# RoboRio_LED_schematic.net
KiCad netlist of a schematic drawn in EAGLE
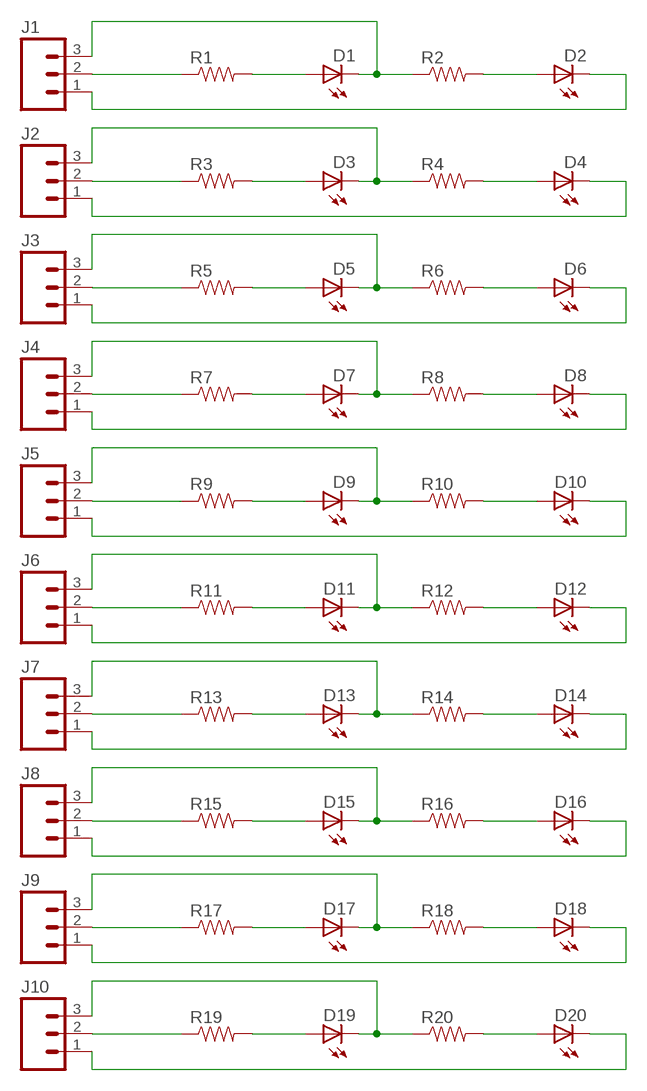
[diagram p0: schematic, sheet 1]

(export (version "E")
  (design (tool "Eeschema 10.0.6"))
  (components
    (comp (ref "D1")
      (value "LED1206")
      (footprint "eagle-import:LED-1206")
      (libsource (lib "eagle-import") (part "LED1206"))
    )
    (comp (ref "D2")
      (value "LED1206")
      (footprint "eagle-import:LED-1206")
      (libsource (lib "eagle-import") (part "LED1206"))
    )
    (comp (ref "D3")
      (value "LED1206")
      (footprint "eagle-import:LED-1206")
      (libsource (lib "eagle-import") (part "LED1206"))
    )
    (comp (ref "D4")
      (value "LED1206")
      (footprint "eagle-import:LED-1206")
      (libsource (lib "eagle-import") (part "LED1206"))
    )
    (comp (ref "D5")
      (value "LED1206")
      (footprint "eagle-import:LED-1206")
      (libsource (lib "eagle-import") (part "LED1206"))
    )
    (comp (ref "D6")
      (value "LED1206")
      (footprint "eagle-import:LED-1206")
      (libsource (lib "eagle-import") (part "LED1206"))
    )
    (comp (ref "D7")
      (value "LED1206")
      (footprint "eagle-import:LED-1206")
      (libsource (lib "eagle-import") (part "LED1206"))
    )
    (comp (ref "D8")
      (value "LED1206")
      (footprint "eagle-import:LED-1206")
      (libsource (lib "eagle-import") (part "LED1206"))
    )
    (comp (ref "D9")
      (value "LED1206")
      (footprint "eagle-import:LED-1206")
      (libsource (lib "eagle-import") (part "LED1206"))
    )
    (comp (ref "D10")
      (value "LED1206")
      (footprint "eagle-import:LED-1206")
      (libsource (lib "eagle-import") (part "LED1206"))
    )
    (comp (ref "D11")
      (value "LED1206")
      (footprint "eagle-import:LED-1206")
      (libsource (lib "eagle-import") (part "LED1206"))
    )
    (comp (ref "D12")
      (value "LED1206")
      (footprint "eagle-import:LED-1206")
      (libsource (lib "eagle-import") (part "LED1206"))
    )
    (comp (ref "D13")
      (value "LED1206")
      (footprint "eagle-import:LED-1206")
      (libsource (lib "eagle-import") (part "LED1206"))
    )
    (comp (ref "D14")
      (value "LED1206")
      (footprint "eagle-import:LED-1206")
      (libsource (lib "eagle-import") (part "LED1206"))
    )
    (comp (ref "D15")
      (value "LED1206")
      (footprint "eagle-import:LED-1206")
      (libsource (lib "eagle-import") (part "LED1206"))
    )
    (comp (ref "D16")
      (value "LED1206")
      (footprint "eagle-import:LED-1206")
      (libsource (lib "eagle-import") (part "LED1206"))
    )
    (comp (ref "D17")
      (value "LED1206")
      (footprint "eagle-import:LED-1206")
      (libsource (lib "eagle-import") (part "LED1206"))
    )
    (comp (ref "D18")
      (value "LED1206")
      (footprint "eagle-import:LED-1206")
      (libsource (lib "eagle-import") (part "LED1206"))
    )
    (comp (ref "D19")
      (value "LED1206")
      (footprint "eagle-import:LED-1206")
      (libsource (lib "eagle-import") (part "LED1206"))
    )
    (comp (ref "D20")
      (value "LED1206")
      (footprint "eagle-import:LED-1206")
      (libsource (lib "eagle-import") (part "LED1206"))
    )
    (comp (ref "J1")
      (value "M03PTH")
      (footprint "eagle-import:1X03")
      (libsource (lib "eagle-import") (part "M03PTH"))
    )
    (comp (ref "J2")
      (value "M03PTH")
      (footprint "eagle-import:1X03")
      (libsource (lib "eagle-import") (part "M03PTH"))
    )
    (comp (ref "J3")
      (value "M03PTH")
      (footprint "eagle-import:1X03")
      (libsource (lib "eagle-import") (part "M03PTH"))
    )
    (comp (ref "J4")
      (value "M03PTH")
      (footprint "eagle-import:1X03")
      (libsource (lib "eagle-import") (part "M03PTH"))
    )
    (comp (ref "J5")
      (value "M03PTH")
      (footprint "eagle-import:1X03")
      (libsource (lib "eagle-import") (part "M03PTH"))
    )
    (comp (ref "J6")
      (value "M03PTH")
      (footprint "eagle-import:1X03")
      (libsource (lib "eagle-import") (part "M03PTH"))
    )
    (comp (ref "J7")
      (value "M03PTH")
      (footprint "eagle-import:1X03")
      (libsource (lib "eagle-import") (part "M03PTH"))
    )
    (comp (ref "J8")
      (value "M03PTH")
      (footprint "eagle-import:1X03")
      (libsource (lib "eagle-import") (part "M03PTH"))
    )
    (comp (ref "J9")
      (value "M03PTH")
      (footprint "eagle-import:1X03")
      (libsource (lib "eagle-import") (part "M03PTH"))
    )
    (comp (ref "J10")
      (value "M03PTH")
      (footprint "eagle-import:1X03")
      (libsource (lib "eagle-import") (part "M03PTH"))
    )
    (comp (ref "R1")
      (value "RESISTOR0603-RES")
      (footprint "eagle-import:0603-RES")
      (libsource (lib "eagle-import") (part "RESISTOR0603-RES"))
    )
    (comp (ref "R2")
      (value "RESISTOR0603-RES")
      (footprint "eagle-import:0603-RES")
      (libsource (lib "eagle-import") (part "RESISTOR0603-RES"))
    )
    (comp (ref "R3")
      (value "RESISTOR0603-RES")
      (footprint "eagle-import:0603-RES")
      (libsource (lib "eagle-import") (part "RESISTOR0603-RES"))
    )
    (comp (ref "R4")
      (value "RESISTOR0603-RES")
      (footprint "eagle-import:0603-RES")
      (libsource (lib "eagle-import") (part "RESISTOR0603-RES"))
    )
    (comp (ref "R5")
      (value "RESISTOR0603-RES")
      (footprint "eagle-import:0603-RES")
      (libsource (lib "eagle-import") (part "RESISTOR0603-RES"))
    )
    (comp (ref "R6")
      (value "RESISTOR0603-RES")
      (footprint "eagle-import:0603-RES")
      (libsource (lib "eagle-import") (part "RESISTOR0603-RES"))
    )
    (comp (ref "R7")
      (value "RESISTOR0603-RES")
      (footprint "eagle-import:0603-RES")
      (libsource (lib "eagle-import") (part "RESISTOR0603-RES"))
    )
    (comp (ref "R8")
      (value "RESISTOR0603-RES")
      (footprint "eagle-import:0603-RES")
      (libsource (lib "eagle-import") (part "RESISTOR0603-RES"))
    )
    (comp (ref "R9")
      (value "RESISTOR0603-RES")
      (footprint "eagle-import:0603-RES")
      (libsource (lib "eagle-import") (part "RESISTOR0603-RES"))
    )
    (comp (ref "R10")
      (value "RESISTOR0603-RES")
      (footprint "eagle-import:0603-RES")
      (libsource (lib "eagle-import") (part "RESISTOR0603-RES"))
    )
    (comp (ref "R11")
      (value "RESISTOR0603-RES")
      (footprint "eagle-import:0603-RES")
      (libsource (lib "eagle-import") (part "RESISTOR0603-RES"))
    )
    (comp (ref "R12")
      (value "RESISTOR0603-RES")
      (footprint "eagle-import:0603-RES")
      (libsource (lib "eagle-import") (part "RESISTOR0603-RES"))
    )
    (comp (ref "R13")
      (value "RESISTOR0603-RES")
      (footprint "eagle-import:0603-RES")
      (libsource (lib "eagle-import") (part "RESISTOR0603-RES"))
    )
    (comp (ref "R14")
      (value "RESISTOR0603-RES")
      (footprint "eagle-import:0603-RES")
      (libsource (lib "eagle-import") (part "RESISTOR0603-RES"))
    )
    (comp (ref "R15")
      (value "RESISTOR0603-RES")
      (footprint "eagle-import:0603-RES")
      (libsource (lib "eagle-import") (part "RESISTOR0603-RES"))
    )
    (comp (ref "R16")
      (value "RESISTOR0603-RES")
      (footprint "eagle-import:0603-RES")
      (libsource (lib "eagle-import") (part "RESISTOR0603-RES"))
    )
    (comp (ref "R17")
      (value "RESISTOR0603-RES")
      (footprint "eagle-import:0603-RES")
      (libsource (lib "eagle-import") (part "RESISTOR0603-RES"))
    )
    (comp (ref "R18")
      (value "RESISTOR0603-RES")
      (footprint "eagle-import:0603-RES")
      (libsource (lib "eagle-import") (part "RESISTOR0603-RES"))
    )
    (comp (ref "R19")
      (value "RESISTOR0603-RES")
      (footprint "eagle-import:0603-RES")
      (libsource (lib "eagle-import") (part "RESISTOR0603-RES"))
    )
    (comp (ref "R20")
      (value "RESISTOR0603-RES")
      (footprint "eagle-import:0603-RES")
      (libsource (lib "eagle-import") (part "RESISTOR0603-RES"))
    )
  )
  (nets
    (net (code "1") (name "Net-(D1-PadA)") (class "Default")
      (node (ref "D1") (pin "A") (pinfunction "A_A") (pintype "passive"))
      (node (ref "R1") (pin "2") (pinfunction "2_2") (pintype "passive"))
    )
    (net (code "2") (name "Net-(D1-PadC)") (class "Default")
      (node (ref "D1") (pin "C") (pinfunction "C_C") (pintype "passive"))
      (node (ref "J1") (pin "3") (pinfunction "3_3") (pintype "passive"))
      (node (ref "R2") (pin "1") (pinfunction "1_1") (pintype "passive"))
    )
    (net (code "3") (name "Net-(D2-PadA)") (class "Default")
      (node (ref "D2") (pin "A") (pinfunction "A_A") (pintype "passive"))
      (node (ref "R2") (pin "2") (pinfunction "2_2") (pintype "passive"))
    )
    (net (code "4") (name "Net-(D2-PadC)") (class "Default")
      (node (ref "D2") (pin "C") (pinfunction "C_C") (pintype "passive"))
      (node (ref "J1") (pin "1") (pinfunction "1_1") (pintype "passive"))
    )
    (net (code "5") (name "Net-(D3-PadA)") (class "Default")
      (node (ref "D3") (pin "A") (pinfunction "A_A") (pintype "passive"))
      (node (ref "R3") (pin "2") (pinfunction "2_2") (pintype "passive"))
    )
    (net (code "6") (name "Net-(D3-PadC)") (class "Default")
      (node (ref "D3") (pin "C") (pinfunction "C_C") (pintype "passive"))
      (node (ref "J2") (pin "3") (pinfunction "3_3") (pintype "passive"))
      (node (ref "R4") (pin "1") (pinfunction "1_1") (pintype "passive"))
    )
    (net (code "7") (name "Net-(D4-PadA)") (class "Default")
      (node (ref "D4") (pin "A") (pinfunction "A_A") (pintype "passive"))
      (node (ref "R4") (pin "2") (pinfunction "2_2") (pintype "passive"))
    )
    (net (code "8") (name "Net-(D4-PadC)") (class "Default")
      (node (ref "D4") (pin "C") (pinfunction "C_C") (pintype "passive"))
      (node (ref "J2") (pin "1") (pinfunction "1_1") (pintype "passive"))
    )
    (net (code "9") (name "Net-(D5-PadA)") (class "Default")
      (node (ref "D5") (pin "A") (pinfunction "A_A") (pintype "passive"))
      (node (ref "R5") (pin "2") (pinfunction "2_2") (pintype "passive"))
    )
    (net (code "10") (name "Net-(D5-PadC)") (class "Default")
      (node (ref "D5") (pin "C") (pinfunction "C_C") (pintype "passive"))
      (node (ref "J3") (pin "3") (pinfunction "3_3") (pintype "passive"))
      (node (ref "R6") (pin "1") (pinfunction "1_1") (pintype "passive"))
    )
    (net (code "11") (name "Net-(D6-PadA)") (class "Default")
      (node (ref "D6") (pin "A") (pinfunction "A_A") (pintype "passive"))
      (node (ref "R6") (pin "2") (pinfunction "2_2") (pintype "passive"))
    )
    (net (code "12") (name "Net-(D6-PadC)") (class "Default")
      (node (ref "D6") (pin "C") (pinfunction "C_C") (pintype "passive"))
      (node (ref "J3") (pin "1") (pinfunction "1_1") (pintype "passive"))
    )
    (net (code "13") (name "Net-(D7-PadA)") (class "Default")
      (node (ref "D7") (pin "A") (pinfunction "A_A") (pintype "passive"))
      (node (ref "R7") (pin "2") (pinfunction "2_2") (pintype "passive"))
    )
    (net (code "14") (name "Net-(D7-PadC)") (class "Default")
      (node (ref "D7") (pin "C") (pinfunction "C_C") (pintype "passive"))
      (node (ref "J4") (pin "3") (pinfunction "3_3") (pintype "passive"))
      (node (ref "R8") (pin "1") (pinfunction "1_1") (pintype "passive"))
    )
    (net (code "15") (name "Net-(D8-PadA)") (class "Default")
      (node (ref "D8") (pin "A") (pinfunction "A_A") (pintype "passive"))
      (node (ref "R8") (pin "2") (pinfunction "2_2") (pintype "passive"))
    )
    (net (code "16") (name "Net-(D8-PadC)") (class "Default")
      (node (ref "D8") (pin "C") (pinfunction "C_C") (pintype "passive"))
      (node (ref "J4") (pin "1") (pinfunction "1_1") (pintype "passive"))
    )
    (net (code "17") (name "Net-(D9-PadA)") (class "Default")
      (node (ref "D9") (pin "A") (pinfunction "A_A") (pintype "passive"))
      (node (ref "R9") (pin "2") (pinfunction "2_2") (pintype "passive"))
    )
    (net (code "18") (name "Net-(D9-PadC)") (class "Default")
      (node (ref "D9") (pin "C") (pinfunction "C_C") (pintype "passive"))
      (node (ref "J5") (pin "3") (pinfunction "3_3") (pintype "passive"))
      (node (ref "R10") (pin "1") (pinfunction "1_1") (pintype "passive"))
    )
    (net (code "19") (name "Net-(D10-PadA)") (class "Default")
      (node (ref "D10") (pin "A") (pinfunction "A_A") (pintype "passive"))
      (node (ref "R10") (pin "2") (pinfunction "2_2") (pintype "passive"))
    )
    (net (code "20") (name "Net-(D10-PadC)") (class "Default")
      (node (ref "D10") (pin "C") (pinfunction "C_C") (pintype "passive"))
      (node (ref "J5") (pin "1") (pinfunction "1_1") (pintype "passive"))
    )
    (net (code "21") (name "Net-(D11-PadA)") (class "Default")
      (node (ref "D11") (pin "A") (pinfunction "A_A") (pintype "passive"))
      (node (ref "R11") (pin "2") (pinfunction "2_2") (pintype "passive"))
    )
    (net (code "22") (name "Net-(D11-PadC)") (class "Default")
      (node (ref "D11") (pin "C") (pinfunction "C_C") (pintype "passive"))
      (node (ref "J6") (pin "3") (pinfunction "3_3") (pintype "passive"))
      (node (ref "R12") (pin "1") (pinfunction "1_1") (pintype "passive"))
    )
    (net (code "23") (name "Net-(D12-PadA)") (class "Default")
      (node (ref "D12") (pin "A") (pinfunction "A_A") (pintype "passive"))
      (node (ref "R12") (pin "2") (pinfunction "2_2") (pintype "passive"))
    )
    (net (code "24") (name "Net-(D12-PadC)") (class "Default")
      (node (ref "D12") (pin "C") (pinfunction "C_C") (pintype "passive"))
      (node (ref "J6") (pin "1") (pinfunction "1_1") (pintype "passive"))
    )
    (net (code "25") (name "Net-(D13-PadA)") (class "Default")
      (node (ref "D13") (pin "A") (pinfunction "A_A") (pintype "passive"))
      (node (ref "R13") (pin "2") (pinfunction "2_2") (pintype "passive"))
    )
    (net (code "26") (name "Net-(D13-PadC)") (class "Default")
      (node (ref "D13") (pin "C") (pinfunction "C_C") (pintype "passive"))
      (node (ref "J7") (pin "3") (pinfunction "3_3") (pintype "passive"))
      (node (ref "R14") (pin "1") (pinfunction "1_1") (pintype "passive"))
    )
    (net (code "27") (name "Net-(D14-PadA)") (class "Default")
      (node (ref "D14") (pin "A") (pinfunction "A_A") (pintype "passive"))
      (node (ref "R14") (pin "2") (pinfunction "2_2") (pintype "passive"))
    )
    (net (code "28") (name "Net-(D14-PadC)") (class "Default")
      (node (ref "D14") (pin "C") (pinfunction "C_C") (pintype "passive"))
      (node (ref "J7") (pin "1") (pinfunction "1_1") (pintype "passive"))
    )
    (net (code "29") (name "Net-(D15-PadA)") (class "Default")
      (node (ref "D15") (pin "A") (pinfunction "A_A") (pintype "passive"))
      (node (ref "R15") (pin "2") (pinfunction "2_2") (pintype "passive"))
    )
    (net (code "30") (name "Net-(D15-PadC)") (class "Default")
      (node (ref "D15") (pin "C") (pinfunction "C_C") (pintype "passive"))
      (node (ref "J8") (pin "3") (pinfunction "3_3") (pintype "passive"))
      (node (ref "R16") (pin "1") (pinfunction "1_1") (pintype "passive"))
    )
    (net (code "31") (name "Net-(D16-PadA)") (class "Default")
      (node (ref "D16") (pin "A") (pinfunction "A_A") (pintype "passive"))
      (node (ref "R16") (pin "2") (pinfunction "2_2") (pintype "passive"))
    )
    (net (code "32") (name "Net-(D16-PadC)") (class "Default")
      (node (ref "D16") (pin "C") (pinfunction "C_C") (pintype "passive"))
      (node (ref "J8") (pin "1") (pinfunction "1_1") (pintype "passive"))
    )
    (net (code "33") (name "Net-(D17-PadA)") (class "Default")
      (node (ref "D17") (pin "A") (pinfunction "A_A") (pintype "passive"))
      (node (ref "R17") (pin "2") (pinfunction "2_2") (pintype "passive"))
    )
    (net (code "34") (name "Net-(D17-PadC)") (class "Default")
      (node (ref "D17") (pin "C") (pinfunction "C_C") (pintype "passive"))
      (node (ref "J9") (pin "3") (pinfunction "3_3") (pintype "passive"))
      (node (ref "R18") (pin "1") (pinfunction "1_1") (pintype "passive"))
    )
    (net (code "35") (name "Net-(D18-PadA)") (class "Default")
      (node (ref "D18") (pin "A") (pinfunction "A_A") (pintype "passive"))
      (node (ref "R18") (pin "2") (pinfunction "2_2") (pintype "passive"))
    )
    (net (code "36") (name "Net-(D18-PadC)") (class "Default")
      (node (ref "D18") (pin "C") (pinfunction "C_C") (pintype "passive"))
      (node (ref "J9") (pin "1") (pinfunction "1_1") (pintype "passive"))
    )
    (net (code "37") (name "Net-(D19-PadA)") (class "Default")
      (node (ref "D19") (pin "A") (pinfunction "A_A") (pintype "passive"))
      (node (ref "R19") (pin "2") (pinfunction "2_2") (pintype "passive"))
    )
    (net (code "38") (name "Net-(D19-PadC)") (class "Default")
      (node (ref "D19") (pin "C") (pinfunction "C_C") (pintype "passive"))
      (node (ref "J10") (pin "3") (pinfunction "3_3") (pintype "passive"))
      (node (ref "R20") (pin "1") (pinfunction "1_1") (pintype "passive"))
    )
    (net (code "39") (name "Net-(D20-PadA)") (class "Default")
      (node (ref "D20") (pin "A") (pinfunction "A_A") (pintype "passive"))
      (node (ref "R20") (pin "2") (pinfunction "2_2") (pintype "passive"))
    )
    (net (code "40") (name "Net-(D20-PadC)") (class "Default")
      (node (ref "D20") (pin "C") (pinfunction "C_C") (pintype "passive"))
      (node (ref "J10") (pin "1") (pinfunction "1_1") (pintype "passive"))
    )
    (net (code "41") (name "Net-(J1-Pad2)") (class "Default")
      (node (ref "J1") (pin "2") (pinfunction "2_2") (pintype "passive"))
      (node (ref "R1") (pin "1") (pinfunction "1_1") (pintype "passive"))
    )
    (net (code "42") (name "Net-(J2-Pad2)") (class "Default")
      (node (ref "J2") (pin "2") (pinfunction "2_2") (pintype "passive"))
      (node (ref "R3") (pin "1") (pinfunction "1_1") (pintype "passive"))
    )
    (net (code "43") (name "Net-(J3-Pad2)") (class "Default")
      (node (ref "J3") (pin "2") (pinfunction "2_2") (pintype "passive"))
      (node (ref "R5") (pin "1") (pinfunction "1_1") (pintype "passive"))
    )
    (net (code "44") (name "Net-(J4-Pad2)") (class "Default")
      (node (ref "J4") (pin "2") (pinfunction "2_2") (pintype "passive"))
      (node (ref "R7") (pin "1") (pinfunction "1_1") (pintype "passive"))
    )
    (net (code "45") (name "Net-(J5-Pad2)") (class "Default")
      (node (ref "J5") (pin "2") (pinfunction "2_2") (pintype "passive"))
      (node (ref "R9") (pin "1") (pinfunction "1_1") (pintype "passive"))
    )
    (net (code "46") (name "Net-(J6-Pad2)") (class "Default")
      (node (ref "J6") (pin "2") (pinfunction "2_2") (pintype "passive"))
      (node (ref "R11") (pin "1") (pinfunction "1_1") (pintype "passive"))
    )
    (net (code "47") (name "Net-(J7-Pad2)") (class "Default")
      (node (ref "J7") (pin "2") (pinfunction "2_2") (pintype "passive"))
      (node (ref "R13") (pin "1") (pinfunction "1_1") (pintype "passive"))
    )
    (net (code "48") (name "Net-(J8-Pad2)") (class "Default")
      (node (ref "J8") (pin "2") (pinfunction "2_2") (pintype "passive"))
      (node (ref "R15") (pin "1") (pinfunction "1_1") (pintype "passive"))
    )
    (net (code "49") (name "Net-(J9-Pad2)") (class "Default")
      (node (ref "J9") (pin "2") (pinfunction "2_2") (pintype "passive"))
      (node (ref "R17") (pin "1") (pinfunction "1_1") (pintype "passive"))
    )
    (net (code "50") (name "Net-(J10-Pad2)") (class "Default")
      (node (ref "J10") (pin "2") (pinfunction "2_2") (pintype "passive"))
      (node (ref "R19") (pin "1") (pinfunction "1_1") (pintype "passive"))
    )
  )
)
